# Relay_Control.net
KiCad netlist of a schematic drawn in Altium Designer
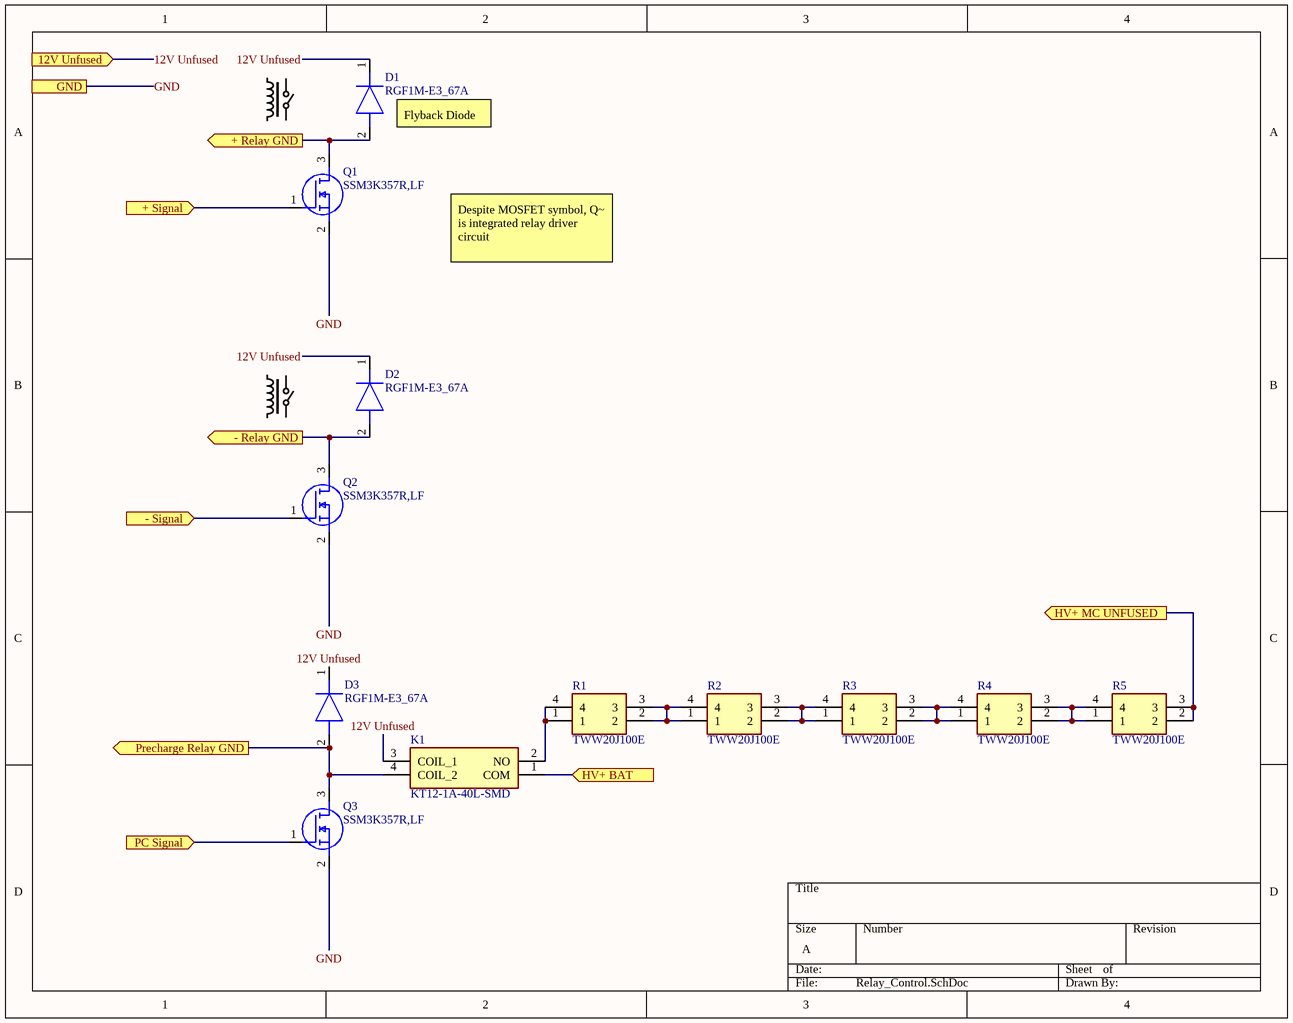
[diagram p0: Relay_Control.SchDoc]

(export (version "E")
  (design (tool "Eeschema 10.0.6"))
  (components
    (comp (ref "D1")
      (value "RGF1M-E3_67A")
      (footprint "SamacSys:DIOM5426X300N")
      (description "Diode")
      (fields
        (field (name "MANUFACTURER_PART_NUMBER") "RGF1M-E3/67A")
        (field (name "MOUSER PART NUMBER") "625-RGF1M-E3")
      )
      (libsource (lib "SamacSys") (part "RGF1M-E3_67A"))
    )
    (comp (ref "D2")
      (value "RGF1M-E3_67A")
      (footprint "SamacSys:DIOM5426X300N")
      (description "Diode")
      (fields
        (field (name "MANUFACTURER_PART_NUMBER") "RGF1M-E3/67A")
        (field (name "MOUSER PART NUMBER") "625-RGF1M-E3")
      )
      (libsource (lib "SamacSys") (part "RGF1M-E3_67A"))
    )
    (comp (ref "D3")
      (value "RGF1M-E3_67A")
      (footprint "SamacSys:DIOM5426X300N")
      (description "Diode")
      (fields
        (field (name "MANUFACTURER_PART_NUMBER") "RGF1M-E3/67A")
        (field (name "MOUSER PART NUMBER") "625-RGF1M-E3")
      )
      (libsource (lib "SamacSys") (part "RGF1M-E3_67A"))
    )
    (comp (ref "K1")
      (value "KT12-1A-40L-SMD")
      (footprint "SamacSys:KT121A40LSMD")
      (description "Relay or Contactor")
      (fields (field (name "MOUSER PART NUMBER") "876-KT12-1A-40L-SMD"))
      (libsource (lib "*") (part "KT12-1A-40L-SMD"))
    )
    (comp (ref "Q1")
      (value "SSM3K357R,LF")
      (footprint "SamacSys:SOTFL95P240X88-3N")
      (description "MOSFET (N-Channel)")
      (fields (field (name "MOUSER PART NUMBER") "757-SSM3K357RLF"))
      (libsource (lib "SamacSys") (part "SSM3K357R,LF"))
    )
    (comp (ref "Q2")
      (value "SSM3K357R,LF")
      (footprint "SamacSys:SOTFL95P240X88-3N")
      (description "MOSFET (N-Channel)")
      (fields (field (name "MOUSER PART NUMBER") "757-SSM3K357RLF"))
      (libsource (lib "SamacSys") (part "SSM3K357R,LF"))
    )
    (comp (ref "Q3")
      (value "SSM3K357R,LF")
      (footprint "SamacSys:SOTFL95P240X88-3N")
      (description "MOSFET (N-Channel)")
      (fields (field (name "MOUSER PART NUMBER") "757-SSM3K357RLF"))
      (libsource (lib "SamacSys") (part "SSM3K357R,LF"))
    )
    (comp (ref "R1")
      (value "TWW20J100E")
      (footprint "SamacSys:TWW20J100E")
      (description "Resistor")
      (fields (field (name "MOUSER PART NUMBER") "588-TWW20J100E"))
      (libsource (lib "*") (part "TWW20J100E"))
    )
    (comp (ref "R2")
      (value "TWW20J100E")
      (footprint "SamacSys:TWW20J100E")
      (description "Resistor")
      (fields (field (name "MOUSER PART NUMBER") "588-TWW20J100E"))
      (libsource (lib "*") (part "TWW20J100E"))
    )
    (comp (ref "R3")
      (value "TWW20J100E")
      (footprint "SamacSys:TWW20J100E")
      (description "Resistor")
      (fields (field (name "MOUSER PART NUMBER") "588-TWW20J100E"))
      (libsource (lib "*") (part "TWW20J100E"))
    )
    (comp (ref "R4")
      (value "TWW20J100E")
      (footprint "SamacSys:TWW20J100E")
      (description "Resistor")
      (fields (field (name "MOUSER PART NUMBER") "588-TWW20J100E"))
      (libsource (lib "*") (part "TWW20J100E"))
    )
    (comp (ref "R5")
      (value "TWW20J100E")
      (footprint "SamacSys:TWW20J100E")
      (description "Resistor")
      (fields (field (name "MOUSER PART NUMBER") "588-TWW20J100E"))
      (libsource (lib "*") (part "TWW20J100E"))
    )
  )
  (nets
    (net (code "1") (name "/+ Relay GND") (class "Default")
      (node (ref "D1") (pin "2") (pinfunction "A_2") (pintype "passive"))
      (node (ref "Q1") (pin "3") (pinfunction "D_3") (pintype "passive"))
    )
    (net (code "2") (name "/+ Signal") (class "Default")
      (node (ref "Q1") (pin "1") (pinfunction "G_1") (pintype "passive"))
    )
    (net (code "3") (name "/- Relay GND") (class "Default")
      (node (ref "D2") (pin "2") (pinfunction "A_2") (pintype "passive"))
      (node (ref "Q2") (pin "3") (pinfunction "D_3") (pintype "passive"))
    )
    (net (code "4") (name "/- Signal") (class "Default")
      (node (ref "Q2") (pin "1") (pinfunction "G_1") (pintype "passive"))
    )
    (net (code "5") (name "/12V Unfused") (class "Default")
      (node (ref "D1") (pin "1") (pinfunction "K_1") (pintype "passive"))
      (node (ref "D2") (pin "1") (pinfunction "K_1") (pintype "passive"))
      (node (ref "D3") (pin "1") (pinfunction "K_1") (pintype "passive"))
      (node (ref "K1") (pin "3") (pinfunction "COIL_1_3") (pintype "passive"))
    )
    (net (code "6") (name "/GND") (class "Default")
      (node (ref "Q1") (pin "2") (pinfunction "S_2") (pintype "passive"))
      (node (ref "Q2") (pin "2") (pinfunction "S_2") (pintype "passive"))
      (node (ref "Q3") (pin "2") (pinfunction "S_2") (pintype "passive"))
    )
    (net (code "7") (name "/HV+ BAT") (class "Default")
      (node (ref "K1") (pin "1") (pinfunction "COM_1") (pintype "passive"))
    )
    (net (code "8") (name "/HV+ MC UNFUSED") (class "Default")
      (node (ref "R5") (pin "2") (pinfunction "2_2") (pintype "passive"))
      (node (ref "R5") (pin "3") (pinfunction "3_3") (pintype "passive"))
    )
    (net (code "9") (name "/PC Signal") (class "Default")
      (node (ref "Q3") (pin "1") (pinfunction "G_1") (pintype "passive"))
    )
    (net (code "10") (name "/Precharge Relay GND") (class "Default")
      (node (ref "D3") (pin "2") (pinfunction "A_2") (pintype "passive"))
      (node (ref "K1") (pin "4") (pinfunction "COIL_2_4") (pintype "passive"))
      (node (ref "Q3") (pin "3") (pinfunction "D_3") (pintype "passive"))
    )
    (net (code "11") (name "Net-(K1-NO)") (class "Default")
      (node (ref "K1") (pin "2") (pinfunction "NO_2") (pintype "passive"))
      (node (ref "R1") (pin "1") (pinfunction "1_1") (pintype "passive"))
      (node (ref "R1") (pin "4") (pinfunction "4_4") (pintype "passive"))
    )
    (net (code "12") (name "Net-(R1-Pad2)") (class "Default")
      (node (ref "R1") (pin "2") (pinfunction "2_2") (pintype "passive"))
      (node (ref "R1") (pin "3") (pinfunction "3_3") (pintype "passive"))
      (node (ref "R2") (pin "1") (pinfunction "1_1") (pintype "passive"))
      (node (ref "R2") (pin "4") (pinfunction "4_4") (pintype "passive"))
    )
    (net (code "13") (name "Net-(R2-Pad2)") (class "Default")
      (node (ref "R2") (pin "2") (pinfunction "2_2") (pintype "passive"))
      (node (ref "R2") (pin "3") (pinfunction "3_3") (pintype "passive"))
      (node (ref "R3") (pin "1") (pinfunction "1_1") (pintype "passive"))
      (node (ref "R3") (pin "4") (pinfunction "4_4") (pintype "passive"))
    )
    (net (code "14") (name "Net-(R3-Pad2)") (class "Default")
      (node (ref "R3") (pin "2") (pinfunction "2_2") (pintype "passive"))
      (node (ref "R3") (pin "3") (pinfunction "3_3") (pintype "passive"))
      (node (ref "R4") (pin "1") (pinfunction "1_1") (pintype "passive"))
      (node (ref "R4") (pin "4") (pinfunction "4_4") (pintype "passive"))
    )
    (net (code "15") (name "Net-(R4-Pad2)") (class "Default")
      (node (ref "R4") (pin "2") (pinfunction "2_2") (pintype "passive"))
      (node (ref "R4") (pin "3") (pinfunction "3_3") (pintype "passive"))
      (node (ref "R5") (pin "1") (pinfunction "1_1") (pintype "passive"))
      (node (ref "R5") (pin "4") (pinfunction "4_4") (pintype "passive"))
    )
  )
)
